# Mis_-_Coin_Battery_CR2032.net
KiCad netlist of a schematic drawn in Altium Designer
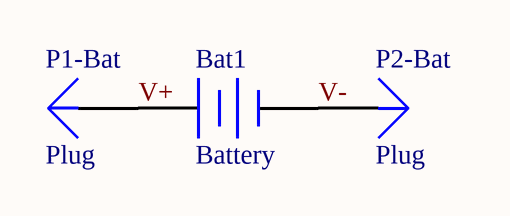
[diagram p0: Mis - Coin Battery CR2032.SchDoc]

(export (version "E")
  (design (tool "Eeschema 10.0.6"))
  (components
    (comp (ref "Bat1")
      (value "Battery")
      (footprint "CR2032 Coin Holder")
      (description "Multicell Battery")
      (fields (field (name "PUBLISHER") "Altium Limited"))
      (libsource (lib "Miscellaneous Devices") (part "Battery"))
    )
    (comp (ref "P1-Bat")
      (value "Plug")
      (footprint "PIN1")
      (fields (field (name "PUBLISHER") "Altium Limited"))
      (libsource (lib "Miscellaneous Connectors") (part "Plug"))
    )
    (comp (ref "P2-Bat")
      (value "Plug")
      (footprint "PIN1")
      (fields (field (name "PUBLISHER") "Altium Limited"))
      (libsource (lib "Miscellaneous Connectors") (part "Plug"))
    )
  )
  (nets
    (net (code "1") (name "/V+") (class "Default")
      (node (ref "Bat1") (pin "1") (pinfunction "+_1") (pintype "passive"))
      (node (ref "P1-Bat") (pin "1") (pinfunction "1_1") (pintype "passive"))
    )
    (net (code "2") (name "/V-") (class "Default")
      (node (ref "Bat1") (pin "2") (pinfunction "-_2") (pintype "passive"))
      (node (ref "P2-Bat") (pin "1") (pinfunction "1_1") (pintype "passive"))
    )
  )
)
